# Additional_PinHeader.net
KiCad netlist of a schematic drawn in Altium Designer
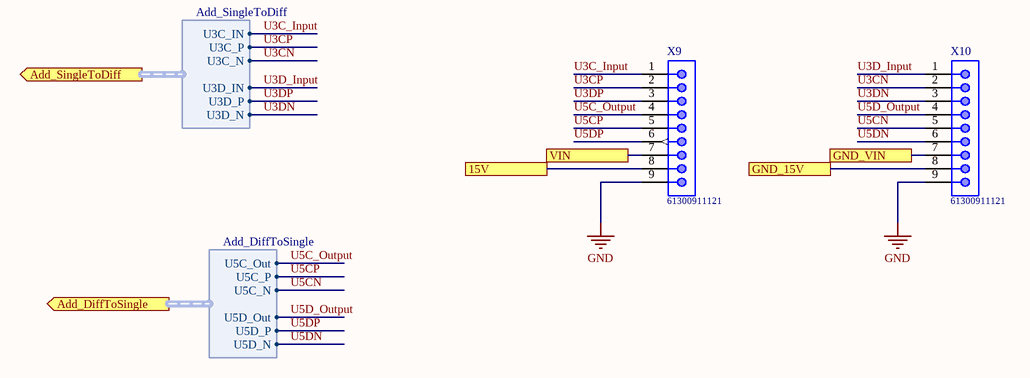
[diagram p0: Additional_PinHeader.SchDoc]

(export (version "E")
  (design (tool "Eeschema 10.0.6"))
  (components
    (comp (ref "X9")
      (value "61300911121")
      (footprint "61300911121")
      (description "Pin Header, 2.54mm, 9 Pins, Single Row")
      (fields (field (name "MANUFACTURER") "WURTH") (field (name "CREATED FROM") "TWilfling"))
      (libsource (lib "user") (part "61300911121"))
    )
    (comp (ref "X10")
      (value "61300911121")
      (footprint "61300911121")
      (description "Pin Header, 2.54mm, 9 Pins, Single Row")
      (fields (field (name "MANUFACTURER") "WURTH") (field (name "CREATED FROM") "TWilfling"))
      (libsource (lib "user") (part "61300911121"))
    )
  )
  (nets
    (net (code "3") (name "/15V") (class "Default")
      (node (ref "X9") (pin "8") (pinfunction "8_8") (pintype "passive"))
    )
    (net (code "4") (name "/GND_15V") (class "Default")
      (node (ref "X10") (pin "8") (pinfunction "8_8") (pintype "passive"))
    )
    (net (code "5") (name "/GND_VIN") (class "Default")
      (node (ref "X10") (pin "7") (pinfunction "7_7") (pintype "passive"))
    )
    (net (code "6") (name "/U3CN") (class "Default")
      (node (ref "X10") (pin "2") (pinfunction "2_2") (pintype "passive"))
    )
    (net (code "7") (name "/U3CP") (class "Default")
      (node (ref "X9") (pin "2") (pinfunction "2_2") (pintype "passive"))
    )
    (net (code "8") (name "/U3C_Input") (class "Default")
      (node (ref "X9") (pin "1") (pinfunction "1_1") (pintype "passive"))
    )
    (net (code "9") (name "/U3DN") (class "Default")
      (node (ref "X10") (pin "3") (pinfunction "3_3") (pintype "passive"))
    )
    (net (code "10") (name "/U3DP") (class "Default")
      (node (ref "X9") (pin "3") (pinfunction "3_3") (pintype "passive"))
    )
    (net (code "11") (name "/U3D_Input") (class "Default")
      (node (ref "X10") (pin "1") (pinfunction "1_1") (pintype "passive"))
    )
    (net (code "12") (name "/U5CN") (class "Default")
      (node (ref "X10") (pin "5") (pinfunction "5_5") (pintype "passive"))
    )
    (net (code "13") (name "/U5CP") (class "Default")
      (node (ref "X9") (pin "5") (pinfunction "5_5") (pintype "passive"))
    )
    (net (code "14") (name "/U5C_Output") (class "Default")
      (node (ref "X9") (pin "4") (pinfunction "4_4") (pintype "passive"))
    )
    (net (code "15") (name "/U5DN") (class "Default")
      (node (ref "X10") (pin "6") (pinfunction "6_6") (pintype "passive"))
    )
    (net (code "16") (name "/U5DP") (class "Default")
      (node (ref "X9") (pin "6") (pinfunction "6_6") (pintype "passive"))
    )
    (net (code "17") (name "/U5D_Output") (class "Default")
      (node (ref "X10") (pin "4") (pinfunction "4_4") (pintype "passive"))
    )
    (net (code "18") (name "/VIN") (class "Default")
      (node (ref "X9") (pin "7") (pinfunction "7_7") (pintype "passive"))
    )
    (net (code "21") (name "GND") (class "Default")
      (node (ref "X10") (pin "9") (pinfunction "9_9") (pintype "passive"))
      (node (ref "X9") (pin "9") (pinfunction "9_9") (pintype "passive"))
    )
  )
)
